# Sheet1.net
KiCad netlist of a schematic drawn in Altium Designer
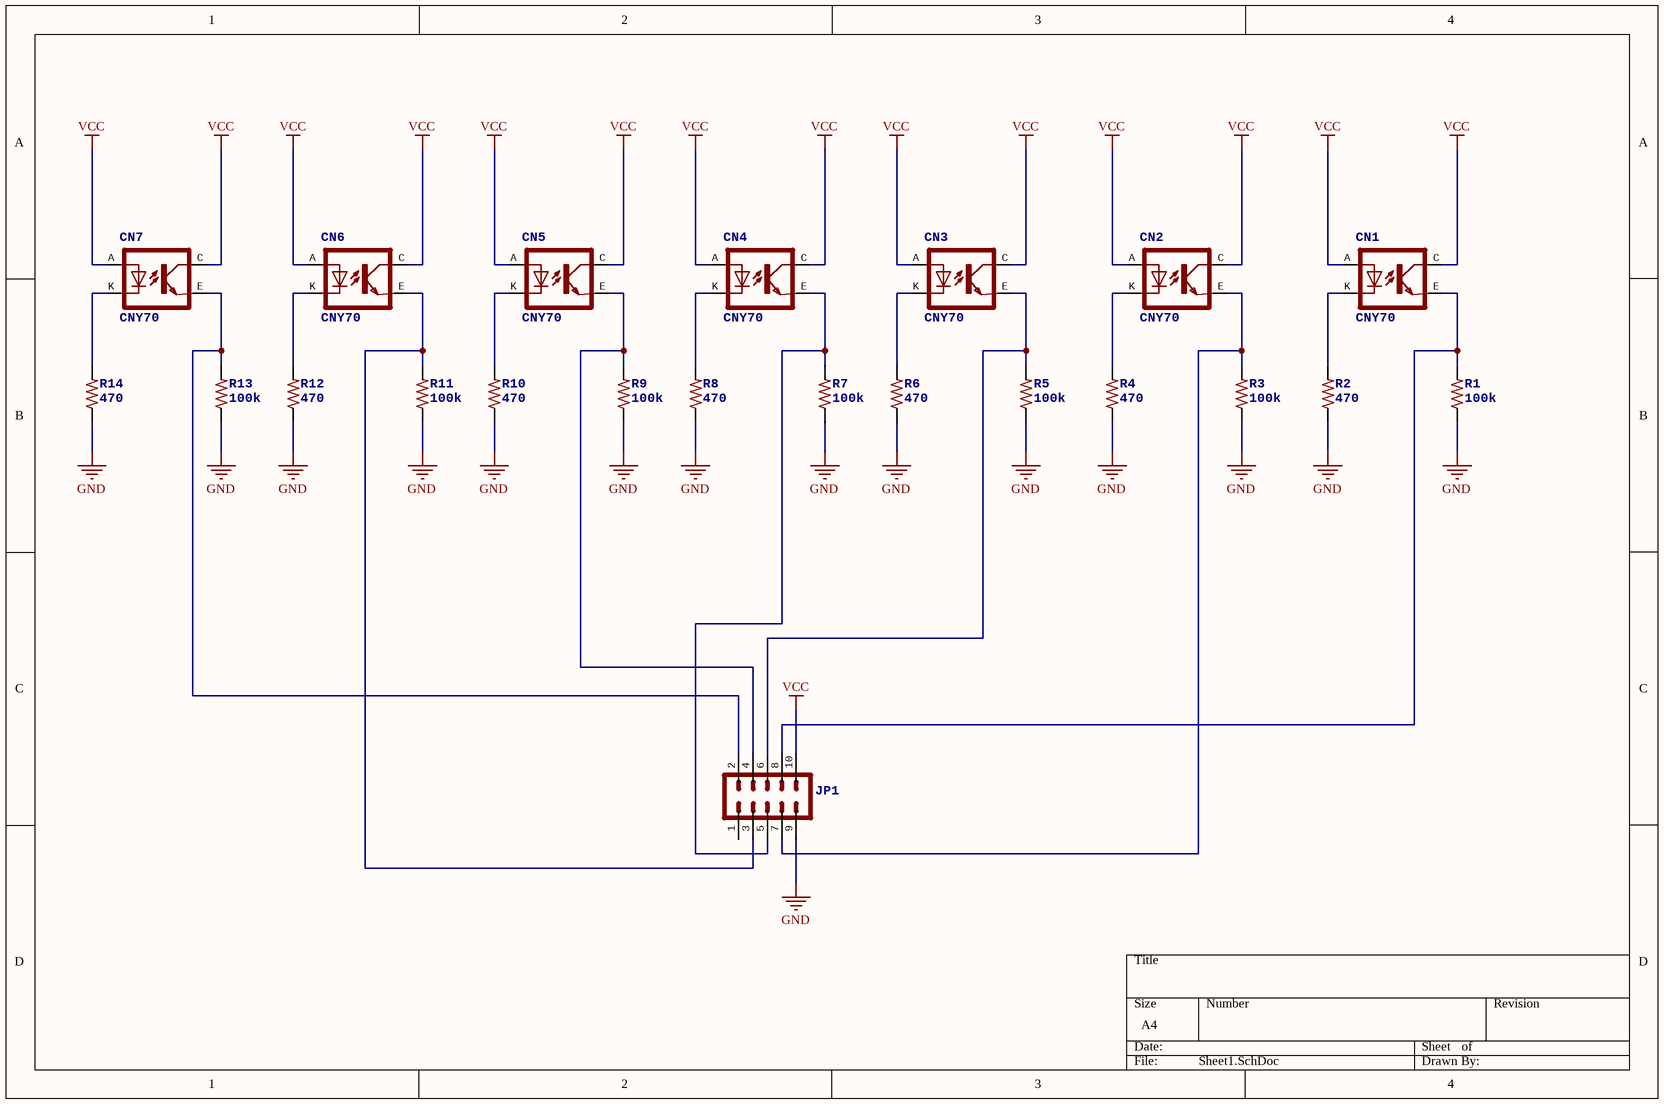
[diagram p0: Sheet1.SchDoc]

(export (version "E")
  (design (tool "Eeschema 10.0.6"))
  (components
    (comp (ref "CN1") (value "CNY70") (footprint "cny70:cny70") (libsource (lib "cny70") (part "CNY70")))
    (comp (ref "CN2") (value "CNY70") (footprint "cny70:cny70") (libsource (lib "cny70") (part "CNY70")))
    (comp (ref "CN3") (value "CNY70") (footprint "cny70:cny70") (libsource (lib "cny70") (part "CNY70")))
    (comp (ref "CN4") (value "CNY70") (footprint "cny70:cny70") (libsource (lib "cny70") (part "CNY70")))
    (comp (ref "CN5") (value "CNY70") (footprint "cny70:cny70") (libsource (lib "cny70") (part "CNY70")))
    (comp (ref "CN6") (value "CNY70") (footprint "cny70:cny70") (libsource (lib "cny70") (part "CNY70")))
    (comp (ref "CN7") (value "CNY70") (footprint "cny70:cny70") (libsource (lib "cny70") (part "CNY70")))
    (comp (ref "JP1")
      (value "Header 5x2Standard 10-pin dual row 0.1\" header. Commonly used with AVR-ISP. Use with Spark Fun Electronics SKU: PRT-00778")
      (footprint "2X5-SHROUDED_LOCK")
      (libsource (lib "SparkFun-Connectors") (part "M05X2SHD_LOCK"))
    )
    (comp (ref "R1")
      (value "100k")
      (footprint "AXIAL-0.4")
      (libsource (lib "SparkFun-Passives") (part "RESISTORPTH-1/4W"))
    )
    (comp (ref "R2")
      (value "470")
      (footprint "AXIAL-0.4")
      (libsource (lib "SparkFun-Passives") (part "RESISTORPTH-1/4W"))
    )
    (comp (ref "R3")
      (value "100k")
      (footprint "AXIAL-0.4")
      (libsource (lib "SparkFun-Passives") (part "RESISTORPTH-1/4W"))
    )
    (comp (ref "R4")
      (value "470")
      (footprint "AXIAL-0.4")
      (libsource (lib "SparkFun-Passives") (part "RESISTORPTH-1/4W"))
    )
    (comp (ref "R5")
      (value "100k")
      (footprint "AXIAL-0.4")
      (libsource (lib "SparkFun-Passives") (part "RESISTORPTH-1/4W"))
    )
    (comp (ref "R6")
      (value "470")
      (footprint "AXIAL-0.4")
      (libsource (lib "SparkFun-Passives") (part "RESISTORPTH-1/4W"))
    )
    (comp (ref "R7")
      (value "100k")
      (footprint "AXIAL-0.4")
      (libsource (lib "SparkFun-Passives") (part "RESISTORPTH-1/4W"))
    )
    (comp (ref "R8")
      (value "470")
      (footprint "AXIAL-0.4")
      (libsource (lib "SparkFun-Passives") (part "RESISTORPTH-1/4W"))
    )
    (comp (ref "R9")
      (value "100k")
      (footprint "AXIAL-0.4")
      (libsource (lib "SparkFun-Passives") (part "RESISTORPTH-1/4W"))
    )
    (comp (ref "R10")
      (value "470")
      (footprint "AXIAL-0.4")
      (libsource (lib "SparkFun-Passives") (part "RESISTORPTH-1/4W"))
    )
    (comp (ref "R11")
      (value "100k")
      (footprint "AXIAL-0.4")
      (libsource (lib "SparkFun-Passives") (part "RESISTORPTH-1/4W"))
    )
    (comp (ref "R12")
      (value "470")
      (footprint "AXIAL-0.4")
      (libsource (lib "SparkFun-Passives") (part "RESISTORPTH-1/4W"))
    )
    (comp (ref "R13")
      (value "100k")
      (footprint "AXIAL-0.4")
      (libsource (lib "SparkFun-Passives") (part "RESISTORPTH-1/4W"))
    )
    (comp (ref "R14")
      (value "470")
      (footprint "AXIAL-0.4")
      (libsource (lib "SparkFun-Passives") (part "RESISTORPTH-1/4W"))
    )
  )
  (nets
    (net (code "1") (name "GND") (class "Default")
      (node (ref "JP1") (pin "9") (pinfunction "9_9") (pintype "passive"))
      (node (ref "R1") (pin "P$1") (pinfunction "1_P$1") (pintype "passive"))
      (node (ref "R10") (pin "P$1") (pinfunction "1_P$1") (pintype "passive"))
      (node (ref "R11") (pin "P$1") (pinfunction "1_P$1") (pintype "passive"))
      (node (ref "R12") (pin "P$1") (pinfunction "1_P$1") (pintype "passive"))
      (node (ref "R13") (pin "P$1") (pinfunction "1_P$1") (pintype "passive"))
      (node (ref "R14") (pin "P$1") (pinfunction "1_P$1") (pintype "passive"))
      (node (ref "R2") (pin "P$1") (pinfunction "1_P$1") (pintype "passive"))
      (node (ref "R3") (pin "P$1") (pinfunction "1_P$1") (pintype "passive"))
      (node (ref "R4") (pin "P$1") (pinfunction "1_P$1") (pintype "passive"))
      (node (ref "R5") (pin "P$1") (pinfunction "1_P$1") (pintype "passive"))
      (node (ref "R6") (pin "P$1") (pinfunction "1_P$1") (pintype "passive"))
      (node (ref "R7") (pin "P$1") (pinfunction "1_P$1") (pintype "passive"))
      (node (ref "R8") (pin "P$1") (pinfunction "1_P$1") (pintype "passive"))
      (node (ref "R9") (pin "P$1") (pinfunction "1_P$1") (pintype "passive"))
    )
    (net (code "2") (name "Net-(CN1-C)") (class "Default")
      (node (ref "CN1") (pin "K") (pinfunction "C_K") (pintype "passive"))
      (node (ref "R2") (pin "P$2") (pinfunction "2_P$2") (pintype "passive"))
    )
    (net (code "3") (name "Net-(CN1-EMI)") (class "Default")
      (node (ref "CN1") (pin "E") (pinfunction "EMI_E") (pintype "passive"))
      (node (ref "JP1") (pin "8") (pinfunction "8_8") (pintype "passive"))
      (node (ref "R1") (pin "P$2") (pinfunction "2_P$2") (pintype "passive"))
    )
    (net (code "4") (name "Net-(CN2-C)") (class "Default")
      (node (ref "CN2") (pin "K") (pinfunction "C_K") (pintype "passive"))
      (node (ref "R4") (pin "P$2") (pinfunction "2_P$2") (pintype "passive"))
    )
    (net (code "5") (name "Net-(CN2-EMI)") (class "Default")
      (node (ref "CN2") (pin "E") (pinfunction "EMI_E") (pintype "passive"))
      (node (ref "JP1") (pin "7") (pinfunction "7_7") (pintype "passive"))
      (node (ref "R3") (pin "P$2") (pinfunction "2_P$2") (pintype "passive"))
    )
    (net (code "6") (name "Net-(CN3-C)") (class "Default")
      (node (ref "CN3") (pin "K") (pinfunction "C_K") (pintype "passive"))
      (node (ref "R6") (pin "P$2") (pinfunction "2_P$2") (pintype "passive"))
    )
    (net (code "7") (name "Net-(CN3-EMI)") (class "Default")
      (node (ref "CN3") (pin "E") (pinfunction "EMI_E") (pintype "passive"))
      (node (ref "JP1") (pin "6") (pinfunction "6_6") (pintype "passive"))
      (node (ref "R5") (pin "P$2") (pinfunction "2_P$2") (pintype "passive"))
    )
    (net (code "8") (name "Net-(CN4-C)") (class "Default")
      (node (ref "CN4") (pin "K") (pinfunction "C_K") (pintype "passive"))
      (node (ref "R8") (pin "P$2") (pinfunction "2_P$2") (pintype "passive"))
    )
    (net (code "9") (name "Net-(CN4-EMI)") (class "Default")
      (node (ref "CN4") (pin "E") (pinfunction "EMI_E") (pintype "passive"))
      (node (ref "JP1") (pin "5") (pinfunction "5_5") (pintype "passive"))
      (node (ref "R7") (pin "P$2") (pinfunction "2_P$2") (pintype "passive"))
    )
    (net (code "10") (name "Net-(CN5-C)") (class "Default")
      (node (ref "CN5") (pin "K") (pinfunction "C_K") (pintype "passive"))
      (node (ref "R10") (pin "P$2") (pinfunction "2_P$2") (pintype "passive"))
    )
    (net (code "11") (name "Net-(CN5-EMI)") (class "Default")
      (node (ref "CN5") (pin "E") (pinfunction "EMI_E") (pintype "passive"))
      (node (ref "JP1") (pin "4") (pinfunction "4_4") (pintype "passive"))
      (node (ref "R9") (pin "P$2") (pinfunction "2_P$2") (pintype "passive"))
    )
    (net (code "12") (name "Net-(CN6-C)") (class "Default")
      (node (ref "CN6") (pin "K") (pinfunction "C_K") (pintype "passive"))
      (node (ref "R12") (pin "P$2") (pinfunction "2_P$2") (pintype "passive"))
    )
    (net (code "13") (name "Net-(CN6-EMI)") (class "Default")
      (node (ref "CN6") (pin "E") (pinfunction "EMI_E") (pintype "passive"))
      (node (ref "JP1") (pin "3") (pinfunction "3_3") (pintype "passive"))
      (node (ref "R11") (pin "P$2") (pinfunction "2_P$2") (pintype "passive"))
    )
    (net (code "14") (name "Net-(CN7-C)") (class "Default")
      (node (ref "CN7") (pin "K") (pinfunction "C_K") (pintype "passive"))
      (node (ref "R14") (pin "P$2") (pinfunction "2_P$2") (pintype "passive"))
    )
    (net (code "15") (name "Net-(CN7-EMI)") (class "Default")
      (node (ref "CN7") (pin "E") (pinfunction "EMI_E") (pintype "passive"))
      (node (ref "JP1") (pin "2") (pinfunction "2_2") (pintype "passive"))
      (node (ref "R13") (pin "P$2") (pinfunction "2_P$2") (pintype "passive"))
    )
    (net (code "16") (name "VCC") (class "Default")
      (node (ref "CN1") (pin "A") (pinfunction "A_A") (pintype "passive"))
      (node (ref "CN1") (pin "C") (pinfunction "COL_C") (pintype "passive"))
      (node (ref "CN2") (pin "A") (pinfunction "A_A") (pintype "passive"))
      (node (ref "CN2") (pin "C") (pinfunction "COL_C") (pintype "passive"))
      (node (ref "CN3") (pin "A") (pinfunction "A_A") (pintype "passive"))
      (node (ref "CN3") (pin "C") (pinfunction "COL_C") (pintype "passive"))
      (node (ref "CN4") (pin "A") (pinfunction "A_A") (pintype "passive"))
      (node (ref "CN4") (pin "C") (pinfunction "COL_C") (pintype "passive"))
      (node (ref "CN5") (pin "A") (pinfunction "A_A") (pintype "passive"))
      (node (ref "CN5") (pin "C") (pinfunction "COL_C") (pintype "passive"))
      (node (ref "CN6") (pin "A") (pinfunction "A_A") (pintype "passive"))
      (node (ref "CN6") (pin "C") (pinfunction "COL_C") (pintype "passive"))
      (node (ref "CN7") (pin "A") (pinfunction "A_A") (pintype "passive"))
      (node (ref "CN7") (pin "C") (pinfunction "COL_C") (pintype "passive"))
      (node (ref "JP1") (pin "10") (pinfunction "10_10") (pintype "passive"))
    )
    (net (code "17") (name "unconnected-(JP1-Pad1)") (class "Default")
      (node (ref "JP1") (pin "1") (pinfunction "1_1") (pintype "passive"))
    )
  )
)
